# ADC.net
KiCad netlist of a schematic drawn in Altium Designer
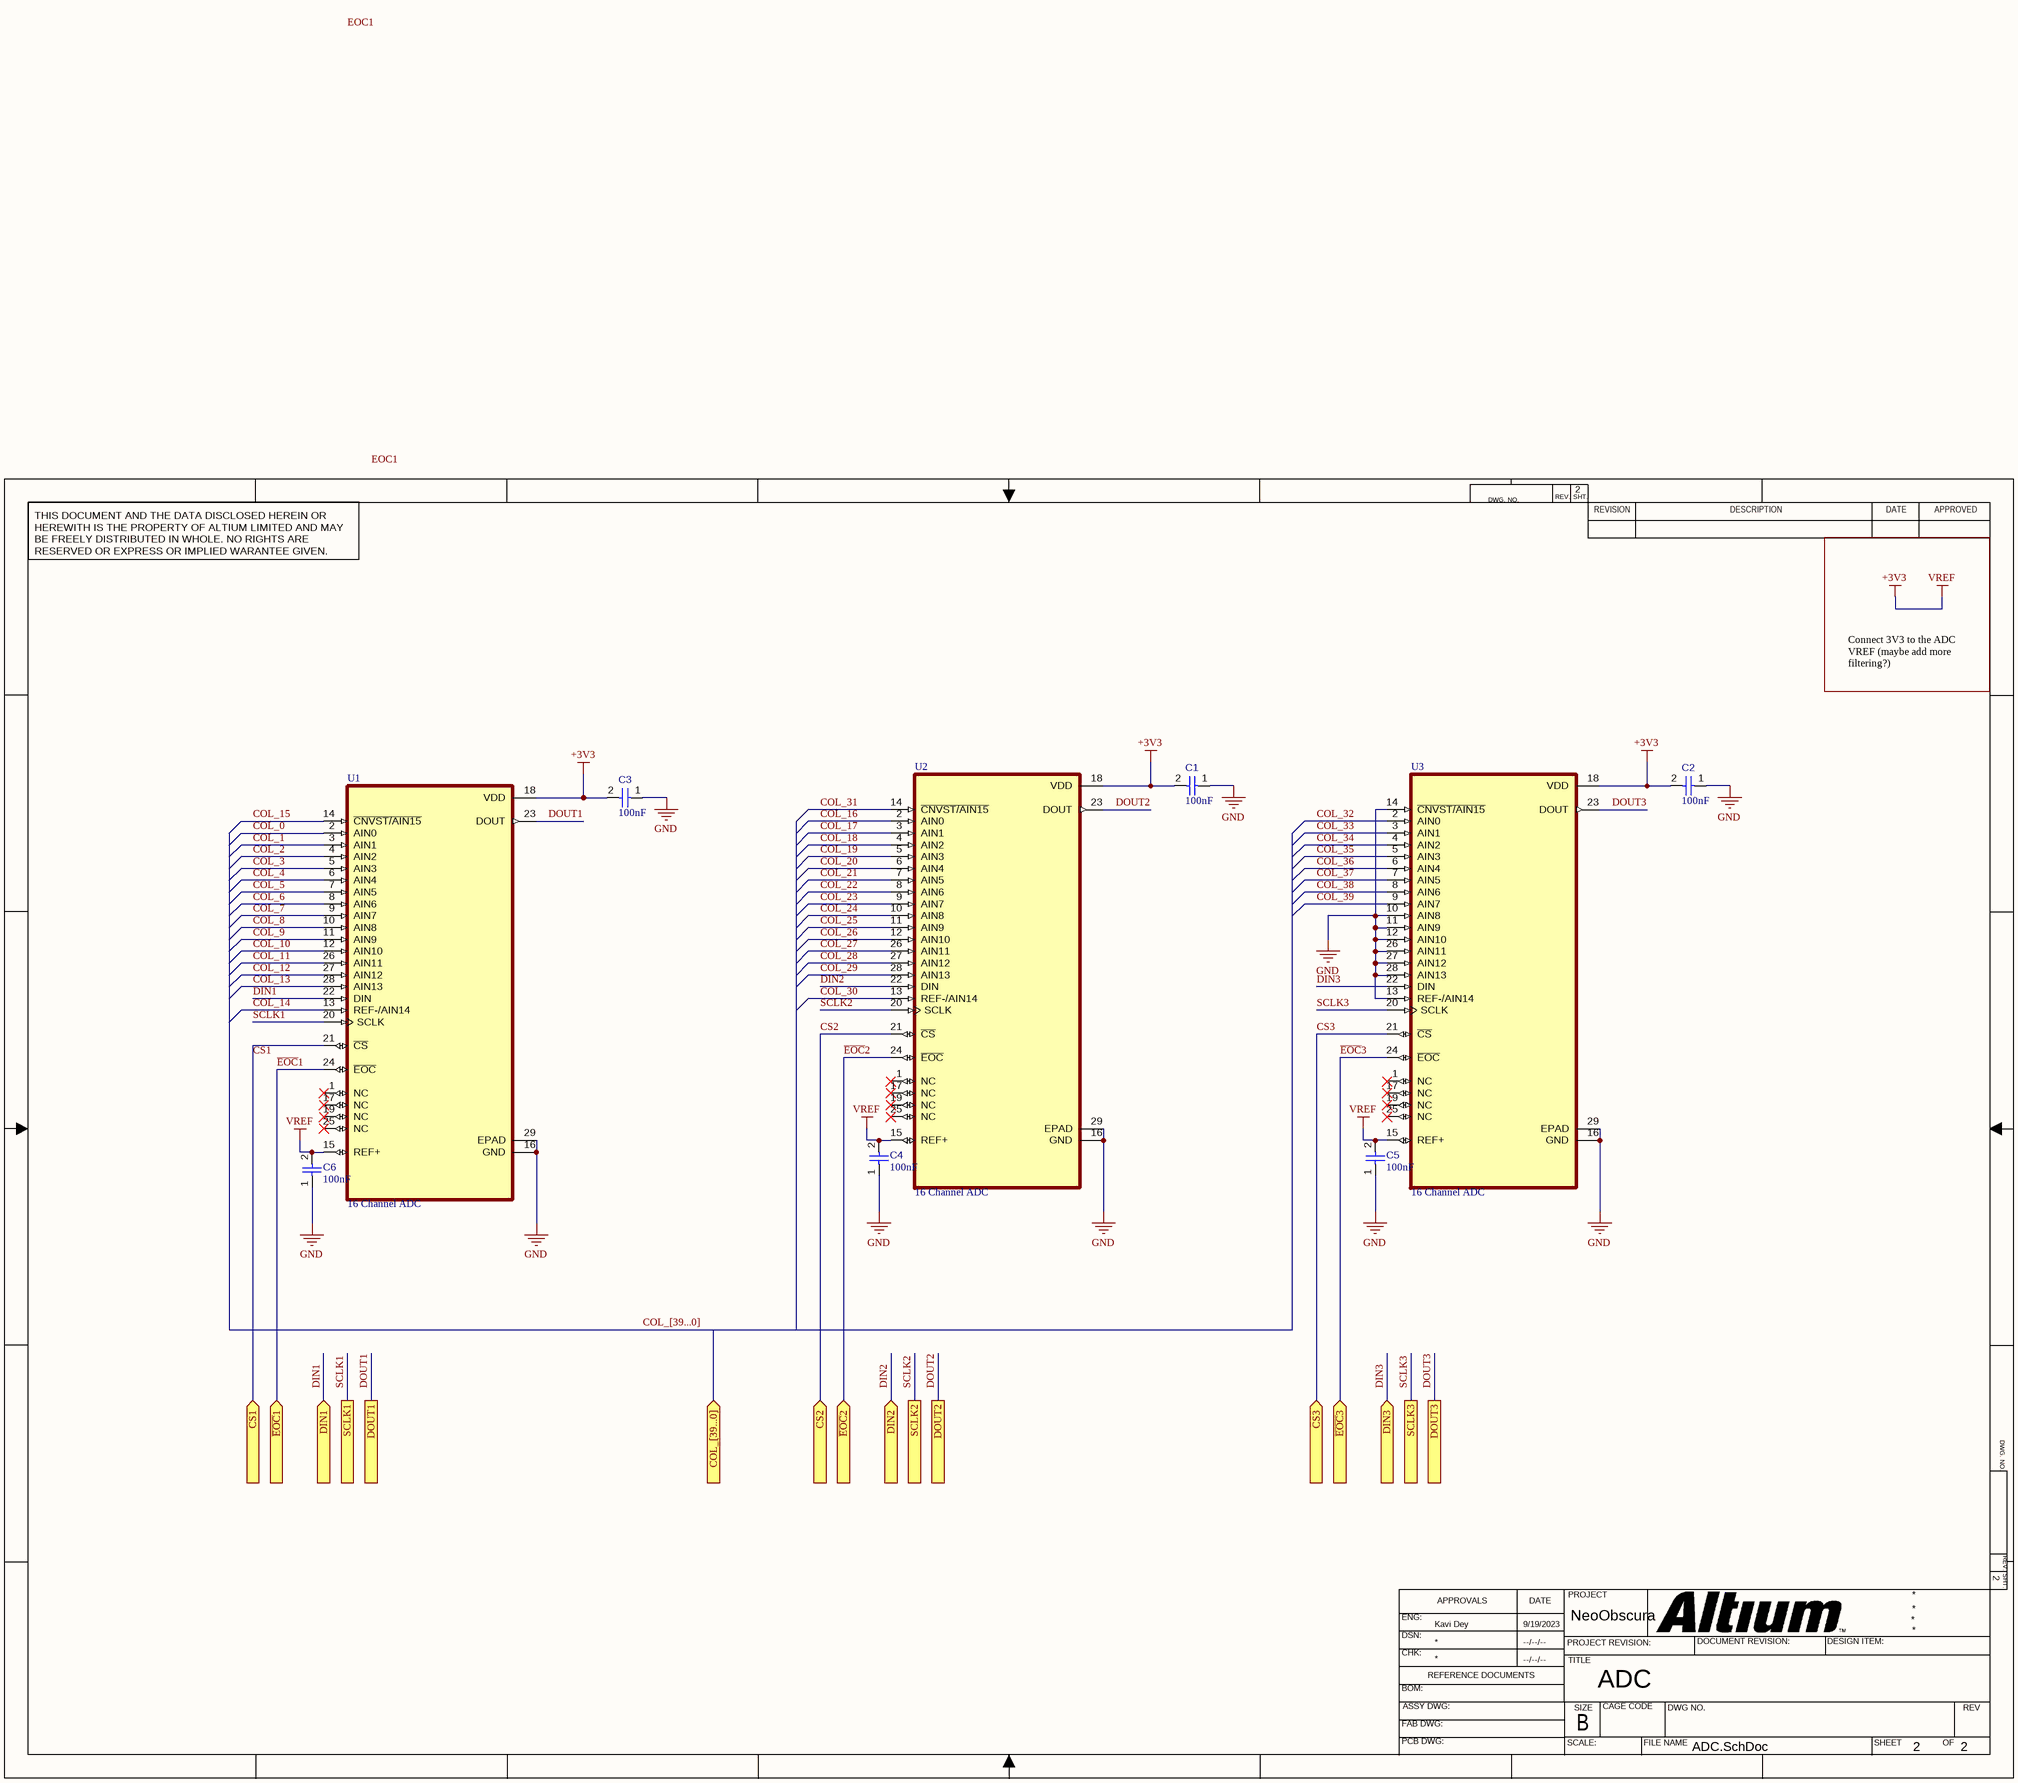
[diagram p0: ADC.SchDoc]

(export (version "E")
  (design (tool "Eeschema 10.0.6"))
  (components
    (comp (ref "C1")
      (value "100nF")
      (footprint "CAPC1005X56X25LL10T15")
      (description "Chip Capacitor, 0.1 uF, +/- 5%, 16 V, 0402 (1005 Metric)")
      (fields (field (name "TOLERANCE") "5%") (field (name "Comment") "Capacitor 0.1 uF +/- 5% 16 V 0402"))
      (libsource (lib "Harvey Mudd") (part "CAP-NP-2"))
    )
    (comp (ref "C2")
      (value "100nF")
      (footprint "CAPC1005X56X25LL10T15")
      (description "Chip Capacitor, 0.1 uF, +/- 5%, 16 V, 0402 (1005 Metric)")
      (fields (field (name "TOLERANCE") "5%") (field (name "Comment") "Capacitor 0.1 uF +/- 5% 16 V 0402"))
      (libsource (lib "Harvey Mudd") (part "CAP-NP-2"))
    )
    (comp (ref "C3")
      (value "100nF")
      (footprint "CAPC1005X56X25LL10T15")
      (description "Chip Capacitor, 0.1 uF, +/- 5%, 16 V, 0402 (1005 Metric)")
      (fields (field (name "TOLERANCE") "5%") (field (name "Comment") "Capacitor 0.1 uF +/- 5% 16 V 0402"))
      (libsource (lib "Harvey Mudd") (part "CAP-NP-2"))
    )
    (comp (ref "C4")
      (value "100nF")
      (footprint "CAPC1005X56X25LL10T15")
      (description "Chip Capacitor, 0.1 uF, +/- 5%, 16 V, 0402 (1005 Metric)")
      (fields (field (name "TOLERANCE") "5%") (field (name "Comment") "Capacitor 0.1 uF +/- 5% 16 V 0402"))
      (libsource (lib "Harvey Mudd") (part "CAP-NP-2"))
    )
    (comp (ref "C5")
      (value "100nF")
      (footprint "CAPC1005X56X25LL10T15")
      (description "Chip Capacitor, 0.1 uF, +/- 5%, 16 V, 0402 (1005 Metric)")
      (fields (field (name "TOLERANCE") "5%") (field (name "Comment") "Capacitor 0.1 uF +/- 5% 16 V 0402"))
      (libsource (lib "Harvey Mudd") (part "CAP-NP-2"))
    )
    (comp (ref "C6")
      (value "100nF")
      (footprint "CAPC1005X56X25LL10T15")
      (description "Chip Capacitor, 0.1 uF, +/- 5%, 16 V, 0402 (1005 Metric)")
      (fields (field (name "TOLERANCE") "5%") (field (name "Comment") "Capacitor 0.1 uF +/- 5% 16 V 0402"))
      (libsource (lib "Harvey Mudd") (part "CAP-NP-2"))
    )
    (comp (ref "U1")
      (value "16 Channel ADC")
      (footprint "QFN50P500X500X80-29N")
      (description "ADC, Successive Approximation, 10-Bit, 1 Func, 16 Channel, Serial Access, BICMOS")
      (fields (field (name "MANUFACTURER") "Maxim") (field (name "MANUFACTURER PART NUMBER") "MAX1031BETI+T"))
      (libsource (lib "NeoObscura") (part "MAX1031BETI+T"))
    )
    (comp (ref "U2")
      (value "16 Channel ADC")
      (footprint "QFN50P500X500X80-29N")
      (description "ADC, Successive Approximation, 10-Bit, 1 Func, 16 Channel, Serial Access, BICMOS")
      (fields (field (name "MANUFACTURER") "Maxim") (field (name "MANUFACTURER PART NUMBER") "MAX1031BETI+T"))
      (libsource (lib "NeoObscura") (part "MAX1031BETI+T"))
    )
    (comp (ref "U3")
      (value "16 Channel ADC")
      (footprint "QFN50P500X500X80-29N")
      (description "ADC, Successive Approximation, 10-Bit, 1 Func, 16 Channel, Serial Access, BICMOS")
      (fields (field (name "MANUFACTURER") "Maxim") (field (name "MANUFACTURER PART NUMBER") "MAX1031BETI+T"))
      (libsource (lib "NeoObscura") (part "MAX1031BETI+T"))
    )
  )
  (nets
    (net (code "2") (name "+3V3") (class "Default")
      (node (ref "C1") (pin "2") (pinfunction "2_2") (pintype "passive"))
      (node (ref "C2") (pin "2") (pinfunction "2_2") (pintype "passive"))
      (node (ref "C3") (pin "2") (pinfunction "2_2") (pintype "passive"))
      (node (ref "C4") (pin "2") (pinfunction "2_2") (pintype "passive"))
      (node (ref "C5") (pin "2") (pinfunction "2_2") (pintype "passive"))
      (node (ref "C6") (pin "2") (pinfunction "2_2") (pintype "passive"))
      (node (ref "U1") (pin "15") (pinfunction "REF+_15") (pintype "bidirectional"))
      (node (ref "U1") (pin "18") (pinfunction "VDD_18") (pintype "power_in"))
      (node (ref "U2") (pin "15") (pinfunction "REF+_15") (pintype "bidirectional"))
      (node (ref "U2") (pin "18") (pinfunction "VDD_18") (pintype "power_in"))
      (node (ref "U3") (pin "15") (pinfunction "REF+_15") (pintype "bidirectional"))
      (node (ref "U3") (pin "18") (pinfunction "VDD_18") (pintype "power_in"))
    )
    (net (code "3") (name "/COL_0") (class "Default")
      (node (ref "U1") (pin "2") (pinfunction "AIN0_2") (pintype "input"))
    )
    (net (code "4") (name "/COL_1") (class "Default")
      (node (ref "U1") (pin "3") (pinfunction "AIN1_3") (pintype "input"))
    )
    (net (code "5") (name "/COL_2") (class "Default")
      (node (ref "U1") (pin "4") (pinfunction "AIN2_4") (pintype "input"))
    )
    (net (code "6") (name "/COL_3") (class "Default")
      (node (ref "U1") (pin "5") (pinfunction "AIN3_5") (pintype "input"))
    )
    (net (code "7") (name "/COL_4") (class "Default")
      (node (ref "U1") (pin "6") (pinfunction "AIN4_6") (pintype "input"))
    )
    (net (code "8") (name "/COL_5") (class "Default")
      (node (ref "U1") (pin "7") (pinfunction "AIN5_7") (pintype "input"))
    )
    (net (code "9") (name "/COL_6") (class "Default")
      (node (ref "U1") (pin "8") (pinfunction "AIN6_8") (pintype "input"))
    )
    (net (code "10") (name "/COL_7") (class "Default")
      (node (ref "U1") (pin "9") (pinfunction "AIN7_9") (pintype "input"))
    )
    (net (code "11") (name "/COL_8") (class "Default")
      (node (ref "U1") (pin "10") (pinfunction "AIN8_10") (pintype "input"))
    )
    (net (code "12") (name "/COL_9") (class "Default")
      (node (ref "U1") (pin "11") (pinfunction "AIN9_11") (pintype "input"))
    )
    (net (code "13") (name "/COL_10") (class "Default")
      (node (ref "U1") (pin "12") (pinfunction "AIN10_12") (pintype "input"))
    )
    (net (code "14") (name "/COL_11") (class "Default")
      (node (ref "U1") (pin "26") (pinfunction "AIN11_26") (pintype "input"))
    )
    (net (code "15") (name "/COL_12") (class "Default")
      (node (ref "U1") (pin "27") (pinfunction "AIN12_27") (pintype "input"))
    )
    (net (code "16") (name "/COL_13") (class "Default")
      (node (ref "U1") (pin "28") (pinfunction "AIN13_28") (pintype "input"))
    )
    (net (code "17") (name "/COL_14") (class "Default")
      (node (ref "U1") (pin "13") (pinfunction "REF-/AIN14_13") (pintype "input"))
    )
    (net (code "18") (name "/COL_15") (class "Default")
      (node (ref "U1") (pin "14") (pinfunction "~{CNVST/AIN15}_14") (pintype "input"))
    )
    (net (code "19") (name "/COL_16") (class "Default")
      (node (ref "U2") (pin "2") (pinfunction "AIN0_2") (pintype "input"))
    )
    (net (code "20") (name "/COL_17") (class "Default")
      (node (ref "U2") (pin "3") (pinfunction "AIN1_3") (pintype "input"))
    )
    (net (code "21") (name "/COL_18") (class "Default")
      (node (ref "U2") (pin "4") (pinfunction "AIN2_4") (pintype "input"))
    )
    (net (code "22") (name "/COL_19") (class "Default")
      (node (ref "U2") (pin "5") (pinfunction "AIN3_5") (pintype "input"))
    )
    (net (code "23") (name "/COL_20") (class "Default")
      (node (ref "U2") (pin "6") (pinfunction "AIN4_6") (pintype "input"))
    )
    (net (code "24") (name "/COL_21") (class "Default")
      (node (ref "U2") (pin "7") (pinfunction "AIN5_7") (pintype "input"))
    )
    (net (code "25") (name "/COL_22") (class "Default")
      (node (ref "U2") (pin "8") (pinfunction "AIN6_8") (pintype "input"))
    )
    (net (code "26") (name "/COL_23") (class "Default")
      (node (ref "U2") (pin "9") (pinfunction "AIN7_9") (pintype "input"))
    )
    (net (code "27") (name "/COL_24") (class "Default")
      (node (ref "U2") (pin "10") (pinfunction "AIN8_10") (pintype "input"))
    )
    (net (code "28") (name "/COL_25") (class "Default")
      (node (ref "U2") (pin "11") (pinfunction "AIN9_11") (pintype "input"))
    )
    (net (code "29") (name "/COL_26") (class "Default")
      (node (ref "U2") (pin "12") (pinfunction "AIN10_12") (pintype "input"))
    )
    (net (code "30") (name "/COL_27") (class "Default")
      (node (ref "U2") (pin "26") (pinfunction "AIN11_26") (pintype "input"))
    )
    (net (code "31") (name "/COL_28") (class "Default")
      (node (ref "U2") (pin "27") (pinfunction "AIN12_27") (pintype "input"))
    )
    (net (code "32") (name "/COL_29") (class "Default")
      (node (ref "U2") (pin "28") (pinfunction "AIN13_28") (pintype "input"))
    )
    (net (code "33") (name "/COL_30") (class "Default")
      (node (ref "U2") (pin "13") (pinfunction "REF-/AIN14_13") (pintype "input"))
    )
    (net (code "34") (name "/COL_31") (class "Default")
      (node (ref "U2") (pin "14") (pinfunction "~{CNVST/AIN15}_14") (pintype "input"))
    )
    (net (code "35") (name "/COL_32") (class "Default")
      (node (ref "U3") (pin "2") (pinfunction "AIN0_2") (pintype "input"))
    )
    (net (code "36") (name "/COL_33") (class "Default")
      (node (ref "U3") (pin "3") (pinfunction "AIN1_3") (pintype "input"))
    )
    (net (code "37") (name "/COL_34") (class "Default")
      (node (ref "U3") (pin "4") (pinfunction "AIN2_4") (pintype "input"))
    )
    (net (code "38") (name "/COL_35") (class "Default")
      (node (ref "U3") (pin "5") (pinfunction "AIN3_5") (pintype "input"))
    )
    (net (code "39") (name "/COL_36") (class "Default")
      (node (ref "U3") (pin "6") (pinfunction "AIN4_6") (pintype "input"))
    )
    (net (code "40") (name "/COL_37") (class "Default")
      (node (ref "U3") (pin "7") (pinfunction "AIN5_7") (pintype "input"))
    )
    (net (code "41") (name "/COL_38") (class "Default")
      (node (ref "U3") (pin "8") (pinfunction "AIN6_8") (pintype "input"))
    )
    (net (code "42") (name "/COL_39") (class "Default")
      (node (ref "U3") (pin "9") (pinfunction "AIN7_9") (pintype "input"))
    )
    (net (code "43") (name "/CS1") (class "Default")
      (node (ref "U1") (pin "21") (pinfunction "~{CS}_21") (pintype "bidirectional"))
    )
    (net (code "44") (name "/CS2") (class "Default")
      (node (ref "U2") (pin "21") (pinfunction "~{CS}_21") (pintype "bidirectional"))
    )
    (net (code "45") (name "/CS3") (class "Default")
      (node (ref "U3") (pin "21") (pinfunction "~{CS}_21") (pintype "bidirectional"))
    )
    (net (code "46") (name "/DIN1") (class "Default")
      (node (ref "U1") (pin "22") (pinfunction "DIN_22") (pintype "input"))
    )
    (net (code "47") (name "/DIN2") (class "Default")
      (node (ref "U2") (pin "22") (pinfunction "DIN_22") (pintype "input"))
    )
    (net (code "48") (name "/DIN3") (class "Default")
      (node (ref "U3") (pin "22") (pinfunction "DIN_22") (pintype "input"))
    )
    (net (code "49") (name "/DOUT1") (class "Default")
      (node (ref "U1") (pin "23") (pinfunction "DOUT_23") (pintype "output"))
    )
    (net (code "50") (name "/DOUT2") (class "Default")
      (node (ref "U2") (pin "23") (pinfunction "DOUT_23") (pintype "output"))
    )
    (net (code "51") (name "/DOUT3") (class "Default")
      (node (ref "U3") (pin "23") (pinfunction "DOUT_23") (pintype "output"))
    )
    (net (code "53") (name "/SCLK1") (class "Default")
      (node (ref "U1") (pin "20") (pinfunction "SCLK_20") (pintype "input"))
    )
    (net (code "54") (name "/SCLK2") (class "Default")
      (node (ref "U2") (pin "20") (pinfunction "SCLK_20") (pintype "input"))
    )
    (net (code "55") (name "/SCLK3") (class "Default")
      (node (ref "U3") (pin "20") (pinfunction "SCLK_20") (pintype "input"))
    )
    (net (code "57") (name "/~{EOC}1") (class "Default")
      (node (ref "U1") (pin "24") (pinfunction "~{EOC}_24") (pintype "bidirectional"))
    )
    (net (code "58") (name "/~{EOC}2") (class "Default")
      (node (ref "U2") (pin "24") (pinfunction "~{EOC}_24") (pintype "bidirectional"))
    )
    (net (code "59") (name "/~{EOC}3") (class "Default")
      (node (ref "U3") (pin "24") (pinfunction "~{EOC}_24") (pintype "bidirectional"))
    )
    (net (code "60") (name "GND") (class "Default")
      (node (ref "C1") (pin "1") (pinfunction "1_1") (pintype "passive"))
      (node (ref "C2") (pin "1") (pinfunction "1_1") (pintype "passive"))
      (node (ref "C3") (pin "1") (pinfunction "1_1") (pintype "passive"))
      (node (ref "C4") (pin "1") (pinfunction "1_1") (pintype "passive"))
      (node (ref "C5") (pin "1") (pinfunction "1_1") (pintype "passive"))
      (node (ref "C6") (pin "1") (pinfunction "1_1") (pintype "passive"))
      (node (ref "U1") (pin "16") (pinfunction "GND_16") (pintype "power_in"))
      (node (ref "U1") (pin "29") (pinfunction "EPAD_29") (pintype "power_in"))
      (node (ref "U2") (pin "16") (pinfunction "GND_16") (pintype "power_in"))
      (node (ref "U2") (pin "29") (pinfunction "EPAD_29") (pintype "power_in"))
      (node (ref "U3") (pin "10") (pinfunction "AIN8_10") (pintype "input"))
      (node (ref "U3") (pin "11") (pinfunction "AIN9_11") (pintype "input"))
      (node (ref "U3") (pin "12") (pinfunction "AIN10_12") (pintype "input"))
      (node (ref "U3") (pin "13") (pinfunction "REF-/AIN14_13") (pintype "input"))
      (node (ref "U3") (pin "14") (pinfunction "~{CNVST/AIN15}_14") (pintype "input"))
      (node (ref "U3") (pin "16") (pinfunction "GND_16") (pintype "power_in"))
      (node (ref "U3") (pin "26") (pinfunction "AIN11_26") (pintype "input"))
      (node (ref "U3") (pin "27") (pinfunction "AIN12_27") (pintype "input"))
      (node (ref "U3") (pin "28") (pinfunction "AIN13_28") (pintype "input"))
      (node (ref "U3") (pin "29") (pinfunction "EPAD_29") (pintype "power_in"))
    )
    (net (code "61") (name "unconnected-(U1-NC-Pad1)") (class "Default")
      (node (ref "U1") (pin "1") (pinfunction "NC_1") (pintype "bidirectional+no_connect"))
    )
    (net (code "62") (name "unconnected-(U1-NC-Pad17)") (class "Default")
      (node (ref "U1") (pin "17") (pinfunction "NC_17") (pintype "bidirectional+no_connect"))
    )
    (net (code "63") (name "unconnected-(U1-NC-Pad19)") (class "Default")
      (node (ref "U1") (pin "19") (pinfunction "NC_19") (pintype "bidirectional+no_connect"))
    )
    (net (code "64") (name "unconnected-(U1-NC-Pad25)") (class "Default")
      (node (ref "U1") (pin "25") (pinfunction "NC_25") (pintype "bidirectional+no_connect"))
    )
    (net (code "65") (name "unconnected-(U2-NC-Pad1)") (class "Default")
      (node (ref "U2") (pin "1") (pinfunction "NC_1") (pintype "bidirectional+no_connect"))
    )
    (net (code "66") (name "unconnected-(U2-NC-Pad17)") (class "Default")
      (node (ref "U2") (pin "17") (pinfunction "NC_17") (pintype "bidirectional+no_connect"))
    )
    (net (code "67") (name "unconnected-(U2-NC-Pad19)") (class "Default")
      (node (ref "U2") (pin "19") (pinfunction "NC_19") (pintype "bidirectional+no_connect"))
    )
    (net (code "68") (name "unconnected-(U2-NC-Pad25)") (class "Default")
      (node (ref "U2") (pin "25") (pinfunction "NC_25") (pintype "bidirectional+no_connect"))
    )
    (net (code "69") (name "unconnected-(U3-NC-Pad1)") (class "Default")
      (node (ref "U3") (pin "1") (pinfunction "NC_1") (pintype "bidirectional+no_connect"))
    )
    (net (code "70") (name "unconnected-(U3-NC-Pad17)") (class "Default")
      (node (ref "U3") (pin "17") (pinfunction "NC_17") (pintype "bidirectional+no_connect"))
    )
    (net (code "71") (name "unconnected-(U3-NC-Pad19)") (class "Default")
      (node (ref "U3") (pin "19") (pinfunction "NC_19") (pintype "bidirectional+no_connect"))
    )
    (net (code "72") (name "unconnected-(U3-NC-Pad25)") (class "Default")
      (node (ref "U3") (pin "25") (pinfunction "NC_25") (pintype "bidirectional+no_connect"))
    )
  )
)
